# mcu.net
KiCad netlist of a schematic drawn in Altium Designer
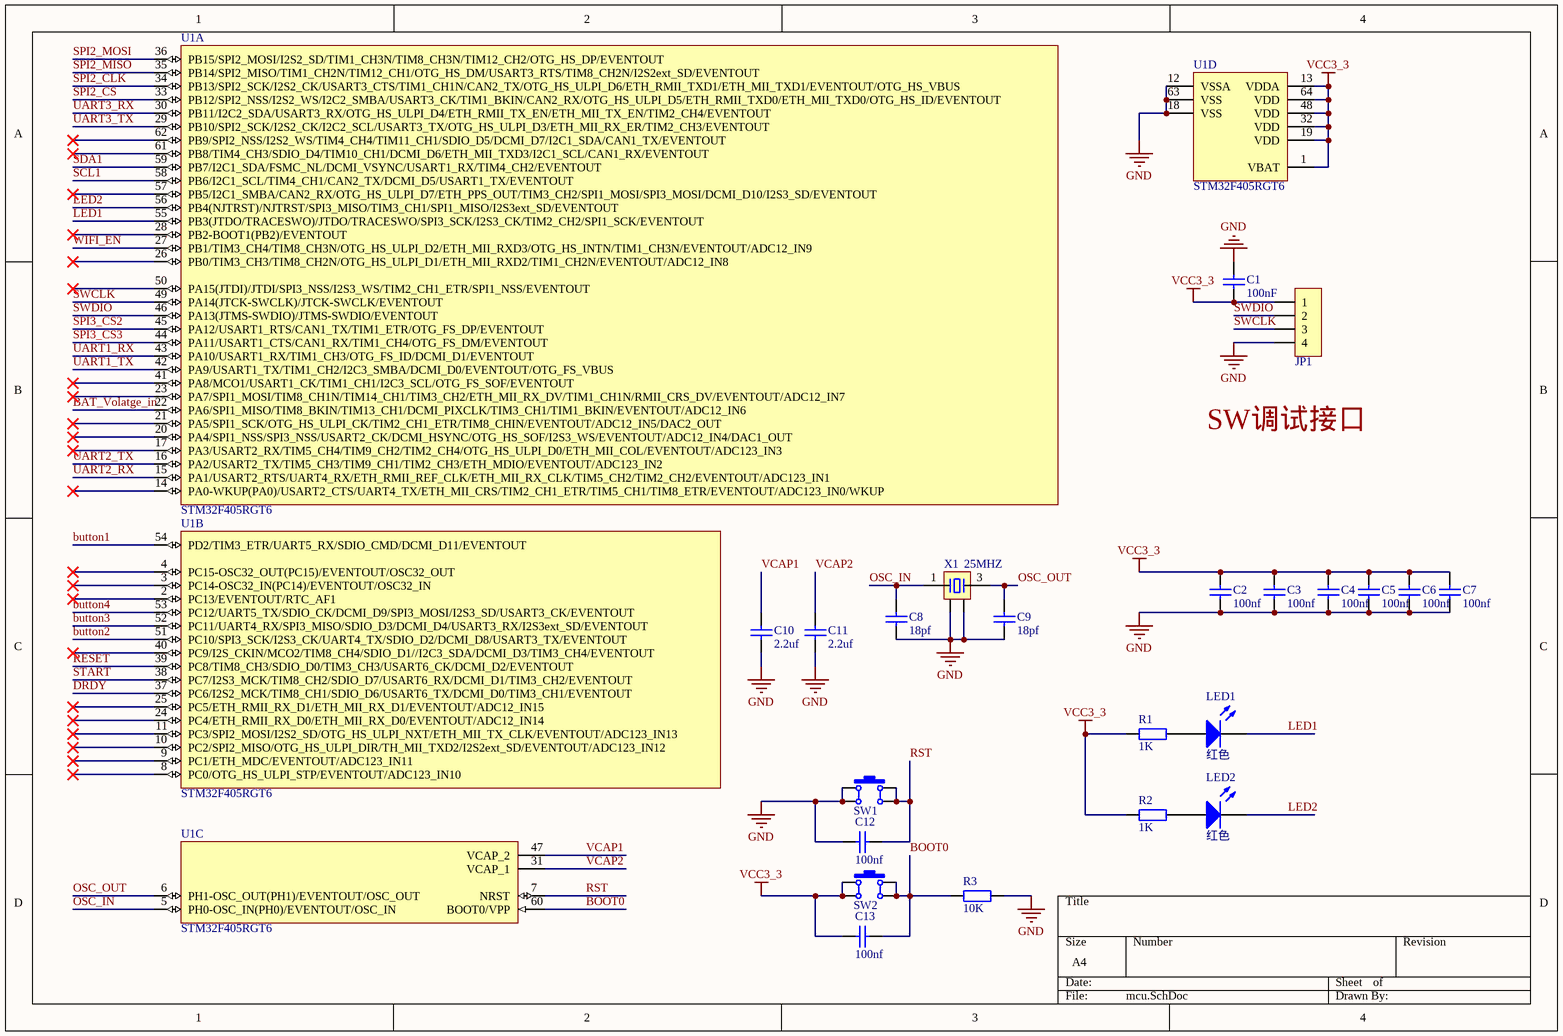
[diagram p0: mcu.SchDoc]

(export (version "E")
  (design (tool "Eeschema 10.0.6"))
  (components
    (comp (ref "C1")
      (value "100nF")
      (footprint "C0603_L")
      (description "贴片电容/MLCC电容")
      (libsource (lib "0.1 - 电阻-电容-电感-保险丝-晶振-晶体-磁珠-电位器-法拉电容-馈通电容") (part "C"))
    )
    (comp (ref "C2")
      (value "100nf")
      (footprint "C0402_L")
      (description "贴片电容/MLCC电容")
      (libsource (lib "0.1 - 电阻-电容-电感-保险丝-晶振-晶体-磁珠-电位器-法拉电容-馈通电容") (part "C"))
    )
    (comp (ref "C3")
      (value "100nf")
      (footprint "C0402_L")
      (description "贴片电容/MLCC电容")
      (libsource (lib "0.1 - 电阻-电容-电感-保险丝-晶振-晶体-磁珠-电位器-法拉电容-馈通电容") (part "C"))
    )
    (comp (ref "C4")
      (value "100nf")
      (footprint "C0402_L")
      (description "贴片电容/MLCC电容")
      (libsource (lib "0.1 - 电阻-电容-电感-保险丝-晶振-晶体-磁珠-电位器-法拉电容-馈通电容") (part "C"))
    )
    (comp (ref "C5")
      (value "100nf")
      (footprint "C0402_L")
      (description "贴片电容/MLCC电容")
      (libsource (lib "0.1 - 电阻-电容-电感-保险丝-晶振-晶体-磁珠-电位器-法拉电容-馈通电容") (part "C"))
    )
    (comp (ref "C6")
      (value "100nf")
      (footprint "C0402_L")
      (description "贴片电容/MLCC电容")
      (libsource (lib "0.1 - 电阻-电容-电感-保险丝-晶振-晶体-磁珠-电位器-法拉电容-馈通电容") (part "C"))
    )
    (comp (ref "C7")
      (value "100nf")
      (footprint "C0402_L")
      (description "贴片电容/MLCC电容")
      (libsource (lib "0.1 - 电阻-电容-电感-保险丝-晶振-晶体-磁珠-电位器-法拉电容-馈通电容") (part "C"))
    )
    (comp (ref "C8")
      (value "18pf")
      (footprint "C0402_L")
      (description "贴片电容/MLCC电容")
      (libsource (lib "0.1 - 电阻-电容-电感-保险丝-晶振-晶体-磁珠-电位器-法拉电容-馈通电容") (part "C"))
    )
    (comp (ref "C9")
      (value "18pf")
      (footprint "C0402_L")
      (description "贴片电容/MLCC电容")
      (libsource (lib "0.1 - 电阻-电容-电感-保险丝-晶振-晶体-磁珠-电位器-法拉电容-馈通电容") (part "C"))
    )
    (comp (ref "C10")
      (value "2.2uf")
      (footprint "C0402_L")
      (description "贴片电容/MLCC电容")
      (libsource (lib "0.1 - 电阻-电容-电感-保险丝-晶振-晶体-磁珠-电位器-法拉电容-馈通电容") (part "C"))
    )
    (comp (ref "C11")
      (value "2.2uf")
      (footprint "C0402_L")
      (description "贴片电容/MLCC电容")
      (libsource (lib "0.1 - 电阻-电容-电感-保险丝-晶振-晶体-磁珠-电位器-法拉电容-馈通电容") (part "C"))
    )
    (comp (ref "C12")
      (value "100nf")
      (footprint "C0603_L")
      (description "贴片电容/MLCC电容")
      (libsource (lib "0.1 - 电阻-电容-电感-保险丝-晶振-晶体-磁珠-电位器-法拉电容-馈通电容") (part "C"))
    )
    (comp (ref "C13")
      (value "100nf")
      (footprint "C0603_L")
      (description "贴片电容/MLCC电容")
      (libsource (lib "0.1 - 电阻-电容-电感-保险丝-晶振-晶体-磁珠-电位器-法拉电容-馈通电容") (part "C"))
    )
    (comp (ref "JP1")
      (value "HDR-1X4")
      (footprint "XH2.54-WI-4P")
      (description "4P接插件")
      (libsource (lib "5.5 - 2.54mm连接器(KF2EDGK_XH2.54_2.54排针排母)") (part "Header 4"))
    )
    (comp (ref "LED1")
      (value "红色")
      (footprint "LED0603_Y")
      (description "贴片LED")
      (libsource (lib "0.3 - LED发光二极管-IR二极管_接收管-光耦") (part "LED"))
    )
    (comp (ref "LED2")
      (value "红色")
      (footprint "LED0603_Y")
      (description "贴片LED")
      (libsource (lib "0.3 - LED发光二极管-IR二极管_接收管-光耦") (part "LED"))
    )
    (comp (ref "R1")
      (value "1K")
      (footprint "R0603_L")
      (description "贴片电阻")
      (libsource (lib "0.1 - 电阻-电容-电感-保险丝-晶振-晶体-磁珠-电位器-法拉电容-馈通电容") (part "R"))
    )
    (comp (ref "R2")
      (value "1K")
      (footprint "R0603_L")
      (description "贴片电阻")
      (libsource (lib "0.1 - 电阻-电容-电感-保险丝-晶振-晶体-磁珠-电位器-法拉电容-馈通电容") (part "R"))
    )
    (comp (ref "R3")
      (value "10K")
      (footprint "R0603_L")
      (description "贴片电阻")
      (libsource (lib "0.1 - 电阻-电容-电感-保险丝-晶振-晶体-磁珠-电位器-法拉电容-馈通电容") (part "R"))
    )
    (comp (ref "SW1")
      (value "3*4*2.5")
      (footprint "SW-SMD-4.2x3.2_4P")
      (description "贴片4脚轻触开关")
      (libsource (lib "0.5 - 按键_开关_蜂鸣器_电池_测试点_Mark点_铜柱") (part "SW SMD-3*4*2.5"))
    )
    (comp (ref "SW2")
      (value "3*4*2.5")
      (footprint "SW-SMD-4.2x3.2_4P")
      (description "贴片4脚轻触开关")
      (libsource (lib "0.5 - 按键_开关_蜂鸣器_电池_测试点_Mark点_铜柱") (part "SW SMD-3*4*2.5"))
    )
    (comp (ref "U1")
      (value "STM32F405RGT6")
      (footprint "TQFP64_V")
      (libsource (lib "2.7 - STM32 F4系列单片机") (part "STM32F405RGT6"))
    )
    (comp (ref "X1")
      (value "25MHZ")
      (footprint "XTAL-3225-4P")
      (description "4脚无源晶振(谐振器）C9006")
      (libsource (lib "0.1 - 电阻-电容-电感-保险丝-晶振-晶体-磁珠-电位器-法拉电容-馈通电容") (part "XTAL-4P"))
    )
  )
  (nets
    (net (code "1") (name "/BAT_Volatge_in") (class "Default")
      (node (ref "U1") (pin "22") (pinfunction "PA6/SPI1_MISO/TIM8_BKIN/TIM13_CH1/DCMI_PIXCLK/TIM3_CH1/TIM1_BKIN/EVENTOUT/ADC12_IN6_22") (pintype "bidirectional"))
    )
    (net (code "2") (name "/BOOT0") (class "Default")
      (node (ref "C13") (pin "1") (pinfunction "1_1") (pintype "passive"))
      (node (ref "R3") (pin "1") (pinfunction "1_1") (pintype "passive"))
      (node (ref "SW2") (pin "2") (pinfunction "2_2") (pintype "passive"))
      (node (ref "SW2") (pin "3") (pinfunction "3_3") (pintype "passive"))
      (node (ref "U1") (pin "60") (pinfunction "BOOT0/VPP_60") (pintype "input"))
    )
    (net (code "3") (name "/DRDY") (class "Default")
      (node (ref "U1") (pin "37") (pinfunction "PC6/I2S2_MCK/TIM8_CH1/SDIO_D6/USART6_TX/DCMI_D0/TIM3_CH1/EVENTOUT_37") (pintype "bidirectional"))
    )
    (net (code "4") (name "/LED1") (class "Default")
      (node (ref "LED1") (pin "2") (pinfunction "K_2") (pintype "passive"))
      (node (ref "U1") (pin "55") (pinfunction "PB3(JTDO/TRACESWO)/JTDO/TRACESWO/SPI3_SCK/I2S3_CK/TIM2_CH2/SPI1_SCK/EVENTOUT_55") (pintype "bidirectional"))
    )
    (net (code "5") (name "/LED2") (class "Default")
      (node (ref "LED2") (pin "2") (pinfunction "K_2") (pintype "passive"))
      (node (ref "U1") (pin "56") (pinfunction "PB4(NJTRST)/NJTRST/SPI3_MISO/TIM3_CH1/SPI1_MISO/I2S3ext_SD/EVENTOUT_56") (pintype "bidirectional"))
    )
    (net (code "6") (name "/OSC_IN") (class "Default")
      (node (ref "C8") (pin "2") (pinfunction "2_2") (pintype "passive"))
      (node (ref "U1") (pin "5") (pinfunction "PH0-OSC_IN(PH0)/EVENTOUT/OSC_IN_5") (pintype "bidirectional"))
      (node (ref "X1") (pin "1") (pinfunction "1_1") (pintype "passive"))
    )
    (net (code "7") (name "/OSC_OUT") (class "Default")
      (node (ref "C9") (pin "2") (pinfunction "2_2") (pintype "passive"))
      (node (ref "U1") (pin "6") (pinfunction "PH1-OSC_OUT(PH1)/EVENTOUT/OSC_OUT_6") (pintype "bidirectional"))
      (node (ref "X1") (pin "3") (pinfunction "3_3") (pintype "passive"))
    )
    (net (code "8") (name "/RESET") (class "Default")
      (node (ref "U1") (pin "39") (pinfunction "PC8/TIM8_CH3/SDIO_D0/TIM3_CH3/USART6_CK/DCMI_D2/EVENTOUT_39") (pintype "bidirectional"))
    )
    (net (code "9") (name "/RST") (class "Default")
      (node (ref "C12") (pin "1") (pinfunction "1_1") (pintype "passive"))
      (node (ref "SW1") (pin "2") (pinfunction "2_2") (pintype "passive"))
      (node (ref "SW1") (pin "3") (pinfunction "3_3") (pintype "passive"))
      (node (ref "U1") (pin "7") (pinfunction "NRST_7") (pintype "bidirectional"))
    )
    (net (code "10") (name "/SCL1") (class "Default")
      (node (ref "U1") (pin "58") (pinfunction "PB6/I2C1_SCL/TIM4_CH1/CAN2_TX/DCMI_D5/USART1_TX/EVENTOUT_58") (pintype "bidirectional"))
    )
    (net (code "11") (name "/SDA1") (class "Default")
      (node (ref "U1") (pin "59") (pinfunction "PB7/I2C1_SDA/FSMC_NL/DCMI_VSYNC/USART1_RX/TIM4_CH2/EVENTOUT_59") (pintype "bidirectional"))
    )
    (net (code "12") (name "/SPI2_CLK") (class "Default")
      (node (ref "U1") (pin "34") (pinfunction "PB13/SPI2_SCK/I2S2_CK/USART3_CTS/TIM1_CH1N/CAN2_TX/OTG_HS_ULPI_D6/ETH_RMII_TXD1/ETH_MII_TXD1/EVENTOUT/OTG_HS_VBUS_34") (pintype "bidirectional"))
    )
    (net (code "13") (name "/SPI2_CS") (class "Default")
      (node (ref "U1") (pin "33") (pinfunction "PB12/SPI2_NSS/I2S2_WS/I2C2_SMBA/USART3_CK/TIM1_BKIN/CAN2_RX/OTG_HS_ULPI_D5/ETH_RMII_TXD0/ETH_MII_TXD0/OTG_HS_ID/EVENTOUT_33") (pintype "bidirectional"))
    )
    (net (code "14") (name "/SPI2_MISO") (class "Default")
      (node (ref "U1") (pin "35") (pinfunction "PB14/SPI2_MISO/TIM1_CH2N/TIM12_CH1/OTG_HS_DM/USART3_RTS/TIM8_CH2N/I2S2ext_SD/EVENTOUT_35") (pintype "bidirectional"))
    )
    (net (code "15") (name "/SPI2_MOSI") (class "Default")
      (node (ref "U1") (pin "36") (pinfunction "PB15/SPI2_MOSI/I2S2_SD/TIM1_CH3N/TIM8_CH3N/TIM12_CH2/OTG_HS_DP/EVENTOUT_36") (pintype "bidirectional"))
    )
    (net (code "16") (name "/SPI3_CS2") (class "Default")
      (node (ref "U1") (pin "45") (pinfunction "PA12/USART1_RTS/CAN1_TX/TIM1_ETR/OTG_FS_DP/EVENTOUT_45") (pintype "bidirectional"))
    )
    (net (code "17") (name "/SPI3_CS3") (class "Default")
      (node (ref "U1") (pin "44") (pinfunction "PA11/USART1_CTS/CAN1_RX/TIM1_CH4/OTG_FS_DM/EVENTOUT_44") (pintype "bidirectional"))
    )
    (net (code "18") (name "/START") (class "Default")
      (node (ref "U1") (pin "38") (pinfunction "PC7/I2S3_MCK/TIM8_CH2/SDIO_D7/USART6_RX/DCMI_D1/TIM3_CH2/EVENTOUT_38") (pintype "bidirectional"))
    )
    (net (code "19") (name "/SWCLK") (class "Default")
      (node (ref "JP1") (pin "3") (pinfunction "3_3") (pintype "passive"))
      (node (ref "U1") (pin "49") (pinfunction "PA14(JTCK-SWCLK)/JTCK-SWCLK/EVENTOUT_49") (pintype "bidirectional"))
    )
    (net (code "20") (name "/SWDIO") (class "Default")
      (node (ref "JP1") (pin "2") (pinfunction "2_2") (pintype "passive"))
      (node (ref "U1") (pin "46") (pinfunction "PA13(JTMS-SWDIO)/JTMS-SWDIO/EVENTOUT_46") (pintype "bidirectional"))
    )
    (net (code "21") (name "/UART1_RX") (class "Default")
      (node (ref "U1") (pin "43") (pinfunction "PA10/USART1_RX/TIM1_CH3/OTG_FS_ID/DCMI_D1/EVENTOUT_43") (pintype "bidirectional"))
    )
    (net (code "22") (name "/UART1_TX") (class "Default")
      (node (ref "U1") (pin "42") (pinfunction "PA9/USART1_TX/TIM1_CH2/I2C3_SMBA/DCMI_D0/EVENTOUT/OTG_FS_VBUS_42") (pintype "bidirectional"))
    )
    (net (code "23") (name "/UART2_RX") (class "Default")
      (node (ref "U1") (pin "15") (pinfunction "PA1/USART2_RTS/UART4_RX/ETH_RMII_REF_CLK/ETH_MII_RX_CLK/TIM5_CH2/TIM2_CH2/EVENTOUT/ADC123_IN1_15") (pintype "bidirectional"))
    )
    (net (code "24") (name "/UART2_TX") (class "Default")
      (node (ref "U1") (pin "16") (pinfunction "PA2/USART2_TX/TIM5_CH3/TIM9_CH1/TIM2_CH3/ETH_MDIO/EVENTOUT/ADC123_IN2_16") (pintype "bidirectional"))
    )
    (net (code "25") (name "/UART3_RX") (class "Default")
      (node (ref "U1") (pin "30") (pinfunction "PB11/I2C2_SDA/USART3_RX/OTG_HS_ULPI_D4/ETH_RMII_TX_EN/ETH_MII_TX_EN/TIM2_CH4/EVENTOUT_30") (pintype "bidirectional"))
    )
    (net (code "26") (name "/UART3_TX") (class "Default")
      (node (ref "U1") (pin "29") (pinfunction "PB10/SPI2_SCK/I2S2_CK/I2C2_SCL/USART3_TX/OTG_HS_ULPI_D3/ETH_MII_RX_ER/TIM2_CH3/EVENTOUT_29") (pintype "bidirectional"))
    )
    (net (code "27") (name "/VCAP1") (class "Default")
      (node (ref "C10") (pin "2") (pinfunction "2_2") (pintype "passive"))
      (node (ref "U1") (pin "47") (pinfunction "VCAP_2_47") (pintype "power_in"))
    )
    (net (code "28") (name "/VCAP2") (class "Default")
      (node (ref "C11") (pin "2") (pinfunction "2_2") (pintype "passive"))
      (node (ref "U1") (pin "31") (pinfunction "VCAP_1_31") (pintype "power_in"))
    )
    (net (code "29") (name "/WIFI_EN") (class "Default")
      (node (ref "U1") (pin "27") (pinfunction "PB1/TIM3_CH4/TIM8_CH3N/OTG_HS_ULPI_D2/ETH_MII_RXD3/OTG_HS_INTN/TIM1_CH3N/EVENTOUT/ADC12_IN9_27") (pintype "bidirectional"))
    )
    (net (code "30") (name "/button1") (class "Default")
      (node (ref "U1") (pin "54") (pinfunction "PD2/TIM3_ETR/UART5_RX/SDIO_CMD/DCMI_D11/EVENTOUT_54") (pintype "bidirectional"))
    )
    (net (code "31") (name "/button2") (class "Default")
      (node (ref "U1") (pin "51") (pinfunction "PC10/SPI3_SCK/I2S3_CK/UART4_TX/SDIO_D2/DCMI_D8/USART3_TX/EVENTOUT_51") (pintype "bidirectional"))
    )
    (net (code "32") (name "/button3") (class "Default")
      (node (ref "U1") (pin "52") (pinfunction "PC11/UART4_RX/SPI3_MISO/SDIO_D3/DCMI_D4/USART3_RX/I2S3ext_SD/EVENTOUT_52") (pintype "bidirectional"))
    )
    (net (code "33") (name "/button4") (class "Default")
      (node (ref "U1") (pin "53") (pinfunction "PC12/UART5_TX/SDIO_CK/DCMI_D9/SPI3_MOSI/I2S3_SD/USART3_CK/EVENTOUT_53") (pintype "bidirectional"))
    )
    (net (code "34") (name "GND") (class "Default")
      (node (ref "C1") (pin "2") (pinfunction "2_2") (pintype "passive"))
      (node (ref "C10") (pin "1") (pinfunction "1_1") (pintype "passive"))
      (node (ref "C11") (pin "1") (pinfunction "1_1") (pintype "passive"))
      (node (ref "C12") (pin "2") (pinfunction "2_2") (pintype "passive"))
      (node (ref "C2") (pin "1") (pinfunction "1_1") (pintype "passive"))
      (node (ref "C3") (pin "1") (pinfunction "1_1") (pintype "passive"))
      (node (ref "C4") (pin "1") (pinfunction "1_1") (pintype "passive"))
      (node (ref "C5") (pin "1") (pinfunction "1_1") (pintype "passive"))
      (node (ref "C6") (pin "1") (pinfunction "1_1") (pintype "passive"))
      (node (ref "C7") (pin "1") (pinfunction "1_1") (pintype "passive"))
      (node (ref "C8") (pin "1") (pinfunction "1_1") (pintype "passive"))
      (node (ref "C9") (pin "1") (pinfunction "1_1") (pintype "passive"))
      (node (ref "JP1") (pin "4") (pinfunction "4_4") (pintype "passive"))
      (node (ref "R3") (pin "2") (pinfunction "2_2") (pintype "passive"))
      (node (ref "SW1") (pin "1") (pinfunction "1_1") (pintype "passive"))
      (node (ref "SW1") (pin "4") (pinfunction "4_4") (pintype "passive"))
      (node (ref "U1") (pin "12") (pinfunction "VSSA_12") (pintype "power_in"))
      (node (ref "U1") (pin "18") (pinfunction "VSS_18") (pintype "power_in"))
      (node (ref "U1") (pin "63") (pinfunction "VSS_63") (pintype "power_in"))
      (node (ref "X1") (pin "2") (pinfunction "2_2") (pintype "passive"))
      (node (ref "X1") (pin "4") (pinfunction "4_4") (pintype "passive"))
    )
    (net (code "35") (name "Net-(LED1-A)") (class "Default")
      (node (ref "LED1") (pin "1") (pinfunction "A_1") (pintype "passive"))
      (node (ref "R1") (pin "2") (pinfunction "2_2") (pintype "passive"))
    )
    (net (code "36") (name "Net-(LED2-A)") (class "Default")
      (node (ref "LED2") (pin "1") (pinfunction "A_1") (pintype "passive"))
      (node (ref "R2") (pin "2") (pinfunction "2_2") (pintype "passive"))
    )
    (net (code "37") (name "VCC3_3") (class "Default")
      (node (ref "C1") (pin "1") (pinfunction "1_1") (pintype "passive"))
      (node (ref "C13") (pin "2") (pinfunction "2_2") (pintype "passive"))
      (node (ref "C2") (pin "2") (pinfunction "2_2") (pintype "passive"))
      (node (ref "C3") (pin "2") (pinfunction "2_2") (pintype "passive"))
      (node (ref "C4") (pin "2") (pinfunction "2_2") (pintype "passive"))
      (node (ref "C5") (pin "2") (pinfunction "2_2") (pintype "passive"))
      (node (ref "C6") (pin "2") (pinfunction "2_2") (pintype "passive"))
      (node (ref "C7") (pin "2") (pinfunction "2_2") (pintype "passive"))
      (node (ref "JP1") (pin "1") (pinfunction "1_1") (pintype "passive"))
      (node (ref "R1") (pin "1") (pinfunction "1_1") (pintype "passive"))
      (node (ref "R2") (pin "1") (pinfunction "1_1") (pintype "passive"))
      (node (ref "SW2") (pin "1") (pinfunction "1_1") (pintype "passive"))
      (node (ref "SW2") (pin "4") (pinfunction "4_4") (pintype "passive"))
      (node (ref "U1") (pin "1") (pinfunction "VBAT_1") (pintype "power_in"))
      (node (ref "U1") (pin "13") (pinfunction "VDDA_13") (pintype "power_in"))
      (node (ref "U1") (pin "19") (pinfunction "VDD_19") (pintype "power_in"))
      (node (ref "U1") (pin "32") (pinfunction "VDD_32") (pintype "power_in"))
      (node (ref "U1") (pin "48") (pinfunction "VDD_48") (pintype "power_in"))
      (node (ref "U1") (pin "64") (pinfunction "VDD_64") (pintype "power_in"))
    )
    (net (code "38") (name "unconnected-(U1A-PA0-WKUP(PA0){slash}USART2_CTS{slash}UART4_TX{slash}ETH_MII_CRS{slash}TIM2_CH1_ETR{slash}TIM5_CH1{slash}TIM8_ETR{slash}EVENTOUT{slash}ADC123_IN0{slash}WKUP-Pad14)") (class "Default")
      (node (ref "U1") (pin "14") (pinfunction "PA0-WKUP(PA0)/USART2_CTS/UART4_TX/ETH_MII_CRS/TIM2_CH1_ETR/TIM5_CH1/TIM8_ETR/EVENTOUT/ADC123_IN0/WKUP_14") (pintype "bidirectional+no_connect"))
    )
    (net (code "39") (name "unconnected-(U1A-PA3{slash}USART2_RX{slash}TIM5_CH4{slash}TIM9_CH2{slash}TIM2_CH4{slash}OTG_HS_ULPI_D0{slash}ETH_MII_COL{slash}EVENTOUT{slash}ADC123_IN3-Pad17)") (class "Default")
      (node (ref "U1") (pin "17") (pinfunction "PA3/USART2_RX/TIM5_CH4/TIM9_CH2/TIM2_CH4/OTG_HS_ULPI_D0/ETH_MII_COL/EVENTOUT/ADC123_IN3_17") (pintype "bidirectional+no_connect"))
    )
    (net (code "40") (name "unconnected-(U1A-PA4{slash}SPI1_NSS{slash}SPI3_NSS{slash}USART2_CK{slash}DCMI_HSYNC{slash}OTG_HS_SOF{slash}I2S3_WS{slash}EVENTOUT{slash}ADC12_IN4{slash}DAC1_OUT-Pad20)") (class "Default")
      (node (ref "U1") (pin "20") (pinfunction "PA4/SPI1_NSS/SPI3_NSS/USART2_CK/DCMI_HSYNC/OTG_HS_SOF/I2S3_WS/EVENTOUT/ADC12_IN4/DAC1_OUT_20") (pintype "bidirectional+no_connect"))
    )
    (net (code "41") (name "unconnected-(U1A-PA5{slash}SPI1_SCK{slash}OTG_HS_ULPI_CK{slash}TIM2_CH1_ETR{slash}TIM8_CHIN{slash}EVENTOUT{slash}ADC12_IN5{slash}DAC2_OUT-Pad21)") (class "Default")
      (node (ref "U1") (pin "21") (pinfunction "PA5/SPI1_SCK/OTG_HS_ULPI_CK/TIM2_CH1_ETR/TIM8_CHIN/EVENTOUT/ADC12_IN5/DAC2_OUT_21") (pintype "bidirectional+no_connect"))
    )
    (net (code "42") (name "unconnected-(U1A-PA7{slash}SPI1_MOSI{slash}TIM8_CH1N{slash}TIM14_CH1{slash}TIM3_CH2{slash}ETH_MII_RX_DV{slash}TIM1_CH1N{slash}RMII_CRS_DV{slash}EVENTOUT{slash}ADC12_IN7-Pad23)") (class "Default")
      (node (ref "U1") (pin "23") (pinfunction "PA7/SPI1_MOSI/TIM8_CH1N/TIM14_CH1/TIM3_CH2/ETH_MII_RX_DV/TIM1_CH1N/RMII_CRS_DV/EVENTOUT/ADC12_IN7_23") (pintype "bidirectional+no_connect"))
    )
    (net (code "43") (name "unconnected-(U1A-PA8{slash}MCO1{slash}USART1_CK{slash}TIM1_CH1{slash}I2C3_SCL{slash}OTG_FS_SOF{slash}EVENTOUT-Pad41)") (class "Default")
      (node (ref "U1") (pin "41") (pinfunction "PA8/MCO1/USART1_CK/TIM1_CH1/I2C3_SCL/OTG_FS_SOF/EVENTOUT_41") (pintype "bidirectional+no_connect"))
    )
    (net (code "44") (name "unconnected-(U1A-PA15(JTDI){slash}JTDI{slash}SPI3_NSS{slash}I2S3_WS{slash}TIM2_CH1_ETR{slash}SPI1_NSS{slash}EVENTOUT-Pad50)") (class "Default")
      (node (ref "U1") (pin "50") (pinfunction "PA15(JTDI)/JTDI/SPI3_NSS/I2S3_WS/TIM2_CH1_ETR/SPI1_NSS/EVENTOUT_50") (pintype "bidirectional+no_connect"))
    )
    (net (code "45") (name "unconnected-(U1A-PB0{slash}TIM3_CH3{slash}TIM8_CH2N{slash}OTG_HS_ULPI_D1{slash}ETH_MII_RXD2{slash}TIM1_CH2N{slash}EVENTOUT{slash}ADC12_IN8-Pad26)") (class "Default")
      (node (ref "U1") (pin "26") (pinfunction "PB0/TIM3_CH3/TIM8_CH2N/OTG_HS_ULPI_D1/ETH_MII_RXD2/TIM1_CH2N/EVENTOUT/ADC12_IN8_26") (pintype "bidirectional+no_connect"))
    )
    (net (code "46") (name "unconnected-(U1A-PB2-BOOT1(PB2){slash}EVENTOUT-Pad28)") (class "Default")
      (node (ref "U1") (pin "28") (pinfunction "PB2-BOOT1(PB2)/EVENTOUT_28") (pintype "bidirectional+no_connect"))
    )
    (net (code "47") (name "unconnected-(U1A-PB5{slash}I2C1_SMBA{slash}CAN2_RX{slash}OTG_HS_ULPI_D7{slash}ETH_PPS_OUT{slash}TIM3_CH2{slash}SPI1_MOSI{slash}SPI3_MOSI{slash}DCMI_D10{slash}I2S3_SD{slash}EVENTOUT-Pad57)") (class "Default")
      (node (ref "U1") (pin "57") (pinfunction "PB5/I2C1_SMBA/CAN2_RX/OTG_HS_ULPI_D7/ETH_PPS_OUT/TIM3_CH2/SPI1_MOSI/SPI3_MOSI/DCMI_D10/I2S3_SD/EVENTOUT_57") (pintype "bidirectional+no_connect"))
    )
    (net (code "48") (name "unconnected-(U1A-PB8{slash}TIM4_CH3{slash}SDIO_D4{slash}TIM10_CH1{slash}DCMI_D6{slash}ETH_MII_TXD3{slash}I2C1_SCL{slash}CAN1_RX{slash}EVENTOUT-Pad61)") (class "Default")
      (node (ref "U1") (pin "61") (pinfunction "PB8/TIM4_CH3/SDIO_D4/TIM10_CH1/DCMI_D6/ETH_MII_TXD3/I2C1_SCL/CAN1_RX/EVENTOUT_61") (pintype "bidirectional+no_connect"))
    )
    (net (code "49") (name "unconnected-(U1A-PB9{slash}SPI2_NSS{slash}I2S2_WS{slash}TIM4_CH4{slash}TIM11_CH1{slash}SDIO_D5{slash}DCMI_D7{slash}I2C1_SDA{slash}CAN1_TX{slash}EVENTOUT-Pad62)") (class "Default")
      (node (ref "U1") (pin "62") (pinfunction "PB9/SPI2_NSS/I2S2_WS/TIM4_CH4/TIM11_CH1/SDIO_D5/DCMI_D7/I2C1_SDA/CAN1_TX/EVENTOUT_62") (pintype "bidirectional+no_connect"))
    )
    (net (code "50") (name "unconnected-(U1B-PC0{slash}OTG_HS_ULPI_STP{slash}EVENTOUT{slash}ADC123_IN10-Pad8)") (class "Default")
      (node (ref "U1") (pin "8") (pinfunction "PC0/OTG_HS_ULPI_STP/EVENTOUT/ADC123_IN10_8") (pintype "bidirectional+no_connect"))
    )
    (net (code "51") (name "unconnected-(U1B-PC1{slash}ETH_MDC{slash}EVENTOUT{slash}ADC123_IN11-Pad9)") (class "Default")
      (node (ref "U1") (pin "9") (pinfunction "PC1/ETH_MDC/EVENTOUT/ADC123_IN11_9") (pintype "bidirectional+no_connect"))
    )
    (net (code "52") (name "unconnected-(U1B-PC2{slash}SPI2_MISO{slash}OTG_HS_ULPI_DIR{slash}TH_MII_TXD2{slash}I2S2ext_SD{slash}EVENTOUT{slash}ADC123_IN12-Pad10)") (class "Default")
      (node (ref "U1") (pin "10") (pinfunction "PC2/SPI2_MISO/OTG_HS_ULPI_DIR/TH_MII_TXD2/I2S2ext_SD/EVENTOUT/ADC123_IN12_10") (pintype "bidirectional+no_connect"))
    )
    (net (code "53") (name "unconnected-(U1B-PC3{slash}SPI2_MOSI{slash}I2S2_SD{slash}OTG_HS_ULPI_NXT{slash}ETH_MII_TX_CLK{slash}EVENTOUT{slash}ADC123_IN13-Pad11)") (class "Default")
      (node (ref "U1") (pin "11") (pinfunction "PC3/SPI2_MOSI/I2S2_SD/OTG_HS_ULPI_NXT/ETH_MII_TX_CLK/EVENTOUT/ADC123_IN13_11") (pintype "bidirectional+no_connect"))
    )
    (net (code "54") (name "unconnected-(U1B-PC4{slash}ETH_RMII_RX_D0{slash}ETH_MII_RX_D0{slash}EVENTOUT{slash}ADC12_IN14-Pad24)") (class "Default")
      (node (ref "U1") (pin "24") (pinfunction "PC4/ETH_RMII_RX_D0/ETH_MII_RX_D0/EVENTOUT/ADC12_IN14_24") (pintype "bidirectional+no_connect"))
    )
    (net (code "55") (name "unconnected-(U1B-PC5{slash}ETH_RMII_RX_D1{slash}ETH_MII_RX_D1{slash}EVENTOUT{slash}ADC12_IN15-Pad25)") (class "Default")
      (node (ref "U1") (pin "25") (pinfunction "PC5/ETH_RMII_RX_D1/ETH_MII_RX_D1/EVENTOUT/ADC12_IN15_25") (pintype "bidirectional+no_connect"))
    )
    (net (code "56") (name "unconnected-(U1B-PC9{slash}I2S_CKIN{slash}MCO2{slash}TIM8_CH4{slash}SDIO_D1{slash}{slash}I2C3_SDA{slash}DCMI_D3{slash}TIM3_CH4{slash}EVENTOUT-Pad40)") (class "Default")
      (node (ref "U1") (pin "40") (pinfunction "PC9/I2S_CKIN/MCO2/TIM8_CH4/SDIO_D1//I2C3_SDA/DCMI_D3/TIM3_CH4/EVENTOUT_40") (pintype "bidirectional+no_connect"))
    )
    (net (code "57") (name "unconnected-(U1B-PC13{slash}EVENTOUT{slash}RTC_AF1-Pad2)") (class "Default")
      (node (ref "U1") (pin "2") (pinfunction "PC13/EVENTOUT/RTC_AF1_2") (pintype "bidirectional+no_connect"))
    )
    (net (code "58") (name "unconnected-(U1B-PC14-OSC32_IN(PC14){slash}EVENTOUT{slash}OSC32_IN-Pad3)") (class "Default")
      (node (ref "U1") (pin "3") (pinfunction "PC14-OSC32_IN(PC14)/EVENTOUT/OSC32_IN_3") (pintype "bidirectional+no_connect"))
    )
    (net (code "59") (name "unconnected-(U1B-PC15-OSC32_OUT(PC15){slash}EVENTOUT{slash}OSC32_OUT-Pad4)") (class "Default")
      (node (ref "U1") (pin "4") (pinfunction "PC15-OSC32_OUT(PC15)/EVENTOUT/OSC32_OUT_4") (pintype "bidirectional+no_connect"))
    )
  )
)
